# jlink.net
KiCad netlist of a schematic drawn in Altium Designer
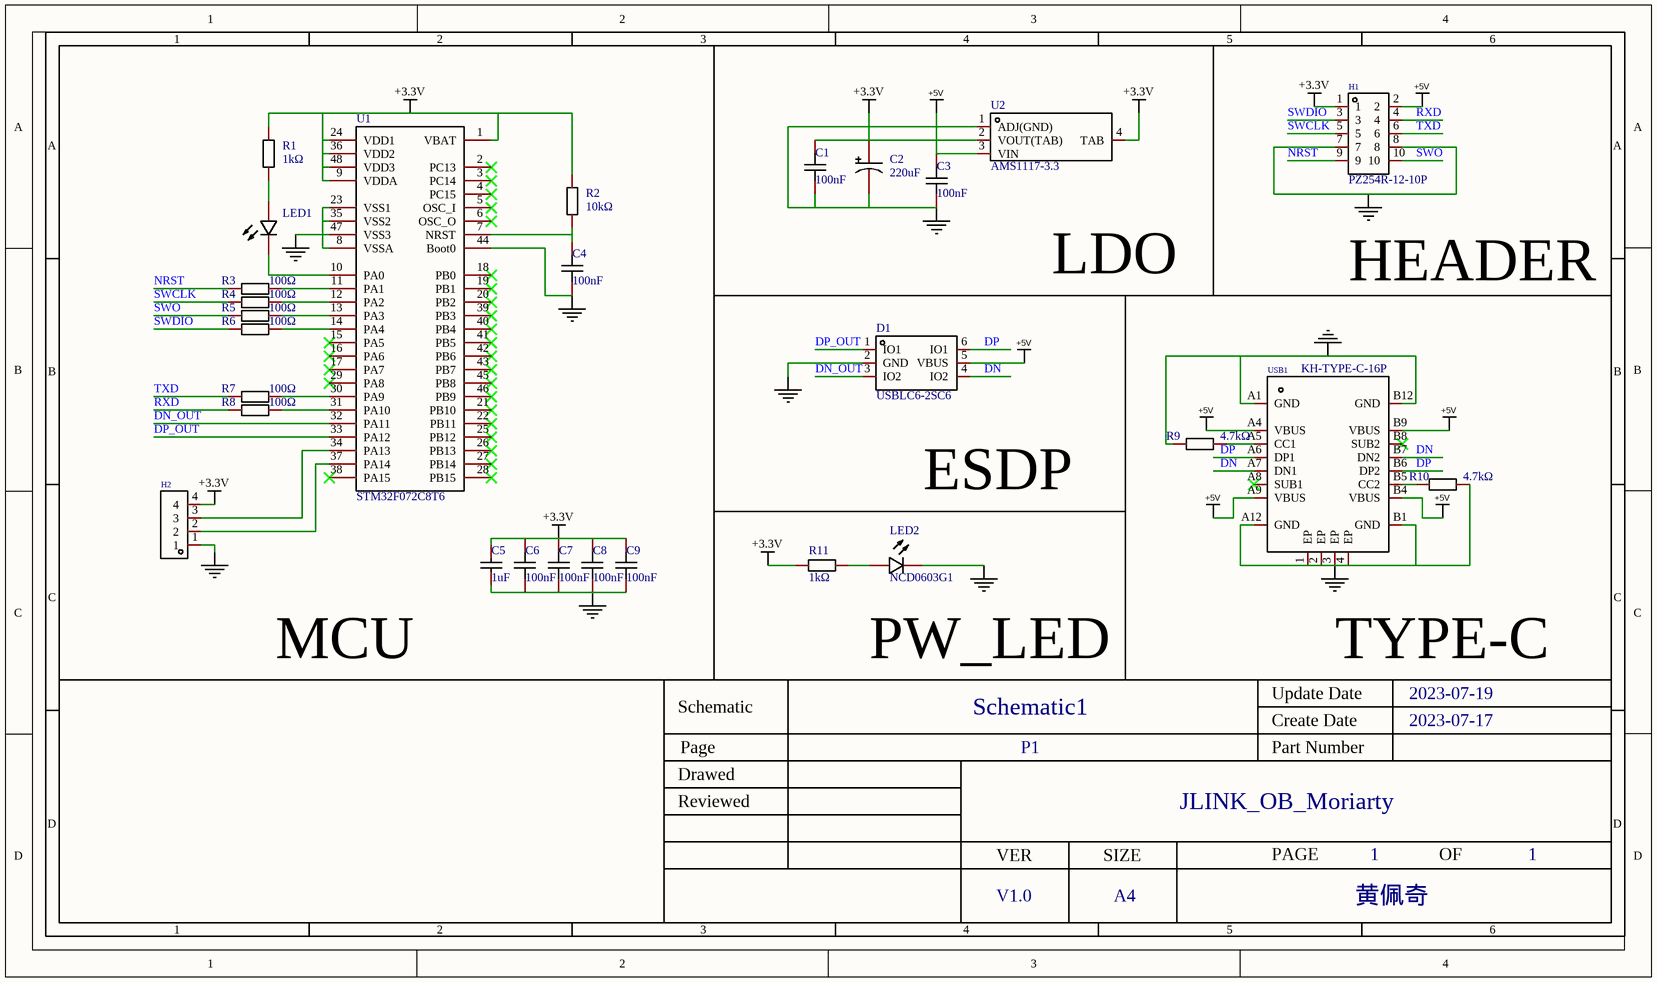
[diagram p0: jlink.schdoc]

(export (version "E")
  (design (tool "Eeschema 10.0.6"))
  (components
    (comp (ref "C1")
      (value "100nF")
      (description "容值:100nF;精度:±10%;额定电压:50V;材质(温度系数):X7R;")
      (fields
        (field (name "NAME") "100nF")
        (field (name "MANUFACTURER") "YAGEO(国巨)")
        (field (name "MANUFACTURER PART") "CC0603KRX7R9BB104")
      )
      (libsource (lib "altium-import") (part "root_1_CC0603KRX7R9BB104_"))
    )
    (comp (ref "C2")
      (value "220uF")
      (description "容值:220uF;精度:±20%;额定电压:50V;电容体直径:10mm;电容体长度:10mm;纹波电流:-;等效串联电阻:-;工作寿命:1000hrs@105℃;工作温度:-45℃~+105℃;")
      (fields
        (field (name "NAME") "220uF")
        (field (name "MANUFACTURER") "Nichicon(尼吉康)")
        (field (name "MANUFACTURER PART") "UWT1H221MNL1GS")
      )
      (libsource (lib "altium-import") (part "root_0_UWT1H221MNL1GS_"))
    )
    (comp (ref "C3")
      (value "100nF")
      (description "容值:100nF;精度:±10%;额定电压:50V;材质(温度系数):X7R;")
      (fields
        (field (name "NAME") "100nF")
        (field (name "MANUFACTURER") "YAGEO(国巨)")
        (field (name "MANUFACTURER PART") "CC0603KRX7R9BB104")
      )
      (libsource (lib "altium-import") (part "root_1_CC0603KRX7R9BB104_"))
    )
    (comp (ref "C4")
      (value "100nF")
      (description "容值:100nF;精度:±10%;额定电压:50V;材质(温度系数):X7R;")
      (fields
        (field (name "NAME") "100nF")
        (field (name "MANUFACTURER") "YAGEO(国巨)")
        (field (name "MANUFACTURER PART") "CC0603KRX7R9BB104")
      )
      (libsource (lib "altium-import") (part "root_1_CC0603KRX7R9BB104_"))
    )
    (comp (ref "C5")
      (value "1uF")
      (description "容值:1uF;精度:±10%;额定电压:25V;材质(温度系数):X7R;")
      (fields
        (field (name "NAME") "1uF")
        (field (name "MANUFACTURER") "FH(风华)")
        (field (name "MANUFACTURER PART") "0603B105K250NT")
      )
      (libsource (lib "altium-import") (part "root_1_0603B105K250NT_"))
    )
    (comp (ref "C6")
      (value "100nF")
      (description "容值:100nF;精度:±10%;额定电压:50V;材质(温度系数):X7R;")
      (fields
        (field (name "NAME") "100nF")
        (field (name "MANUFACTURER") "YAGEO(国巨)")
        (field (name "MANUFACTURER PART") "CC0603KRX7R9BB104")
      )
      (libsource (lib "altium-import") (part "root_1_CC0603KRX7R9BB104_"))
    )
    (comp (ref "C7")
      (value "100nF")
      (description "容值:100nF;精度:±10%;额定电压:50V;材质(温度系数):X7R;")
      (fields
        (field (name "NAME") "100nF")
        (field (name "MANUFACTURER") "YAGEO(国巨)")
        (field (name "MANUFACTURER PART") "CC0603KRX7R9BB104")
      )
      (libsource (lib "altium-import") (part "root_1_CC0603KRX7R9BB104_"))
    )
    (comp (ref "C8")
      (value "100nF")
      (description "容值:100nF;精度:±10%;额定电压:50V;材质(温度系数):X7R;")
      (fields
        (field (name "NAME") "100nF")
        (field (name "MANUFACTURER") "YAGEO(国巨)")
        (field (name "MANUFACTURER PART") "CC0603KRX7R9BB104")
      )
      (libsource (lib "altium-import") (part "root_1_CC0603KRX7R9BB104_"))
    )
    (comp (ref "C9")
      (value "100nF")
      (description "容值:100nF;精度:±10%;额定电压:50V;材质(温度系数):X7R;")
      (fields
        (field (name "NAME") "100nF")
        (field (name "MANUFACTURER") "YAGEO(国巨)")
        (field (name "MANUFACTURER PART") "CC0603KRX7R9BB104")
      )
      (libsource (lib "altium-import") (part "root_1_CC0603KRX7R9BB104_"))
    )
    (comp (ref "D1")
      (value "USBLC6-2SC6")
      (description "USBLC6-2SC6 Vrwm:5V 印记：UL26  ESD静电管静电放电(ESD)保护器件")
      (fields (field (name "NAME") "USBLC6-2SC6") (field (name "MANUFACTURER") "TECH PUBLIC(台舟)"))
      (libsource (lib "altium-import") (part "root_0_USBLC6-2SC6_C2827654_"))
    )
    (comp (ref "H1")
      (value "PZ254R-12-10P")
      (fields (field (name "NAME") "PZ254R-12-10P") (field (name "MANUFACTURER") "XFCN(兴飞)"))
      (libsource (lib "altium-import") (part "root_0_PZ254R-12-10P_"))
    )
    (comp (ref "H2")
      (value "PZ254V-11-04P")
      (fields (field (name "MANUFACTURER") "XFCN(兴飞)"))
      (libsource (lib "altium-import") (part "root_2_PZ254V-11-04P_"))
    )
    (comp (ref "LED1")
      (value "NCD0603W1")
      (description "发光颜色:白灯;")
      (fields (field (name "MANUFACTURER") "国星光电"))
      (libsource (lib "altium-import") (part "root_1_NCD0603W1_"))
    )
    (comp (ref "LED2")
      (value "NCD0603G1")
      (description "发光颜色:翠绿;")
      (fields (field (name "NAME") "NCD0603G1") (field (name "MANUFACTURER") "国星光电"))
      (libsource (lib "altium-import") (part "root_0_NCD0603G1_"))
    )
    (comp (ref "R1")
      (value "1kΩ")
      (description "电阻类型:厚膜电阻;阻值:1kΩ;精度:±1%;功率:100mW;")
      (fields
        (field (name "NAME") "1kΩ")
        (field (name "MANUFACTURER") "UNI-ROYAL(厚声)")
        (field (name "MANUFACTURER PART") "0603WAF1001T5E")
      )
      (libsource (lib "altium-import") (part "root_1_0603WAF1001T5E_"))
    )
    (comp (ref "R2")
      (value "10kΩ")
      (description "电阻类型:厚膜电阻;阻值:10kΩ;精度:±1%;功率:100mW;")
      (fields
        (field (name "NAME") "10kΩ")
        (field (name "MANUFACTURER") "UNI-ROYAL(厚声)")
        (field (name "MANUFACTURER PART") "0603WAF1002T5E")
      )
      (libsource (lib "altium-import") (part "root_1_0603WAF1002T5E_"))
    )
    (comp (ref "R3")
      (value "100Ω")
      (description "电阻类型:厚膜电阻;阻值:100Ω;精度:±1%;功率:100mW;")
      (fields
        (field (name "NAME") "100Ω")
        (field (name "MANUFACTURER") "UNI-ROYAL(厚声)")
        (field (name "MANUFACTURER PART") "0603WAF1000T5E")
      )
      (libsource (lib "altium-import") (part "root_2_0603WAF1000T5E_"))
    )
    (comp (ref "R4")
      (value "100Ω")
      (description "电阻类型:厚膜电阻;阻值:100Ω;精度:±1%;功率:100mW;")
      (fields
        (field (name "NAME") "100Ω")
        (field (name "MANUFACTURER") "UNI-ROYAL(厚声)")
        (field (name "MANUFACTURER PART") "0603WAF1000T5E")
      )
      (libsource (lib "altium-import") (part "root_2_0603WAF1000T5E_"))
    )
    (comp (ref "R5")
      (value "100Ω")
      (description "电阻类型:厚膜电阻;阻值:100Ω;精度:±1%;功率:100mW;")
      (fields
        (field (name "NAME") "100Ω")
        (field (name "MANUFACTURER") "UNI-ROYAL(厚声)")
        (field (name "MANUFACTURER PART") "0603WAF1000T5E")
      )
      (libsource (lib "altium-import") (part "root_2_0603WAF1000T5E_"))
    )
    (comp (ref "R6")
      (value "100Ω")
      (description "电阻类型:厚膜电阻;阻值:100Ω;精度:±1%;功率:100mW;")
      (fields
        (field (name "NAME") "100Ω")
        (field (name "MANUFACTURER") "UNI-ROYAL(厚声)")
        (field (name "MANUFACTURER PART") "0603WAF1000T5E")
      )
      (libsource (lib "altium-import") (part "root_2_0603WAF1000T5E_"))
    )
    (comp (ref "R7")
      (value "100Ω")
      (description "电阻类型:厚膜电阻;阻值:100Ω;精度:±1%;功率:100mW;")
      (fields
        (field (name "NAME") "100Ω")
        (field (name "MANUFACTURER") "UNI-ROYAL(厚声)")
        (field (name "MANUFACTURER PART") "0603WAF1000T5E")
      )
      (libsource (lib "altium-import") (part "root_2_0603WAF1000T5E_"))
    )
    (comp (ref "R8")
      (value "100Ω")
      (description "电阻类型:厚膜电阻;阻值:100Ω;精度:±1%;功率:100mW;")
      (fields
        (field (name "NAME") "100Ω")
        (field (name "MANUFACTURER") "UNI-ROYAL(厚声)")
        (field (name "MANUFACTURER PART") "0603WAF1000T5E")
      )
      (libsource (lib "altium-import") (part "root_2_0603WAF1000T5E_"))
    )
    (comp (ref "R9")
      (value "4.7kΩ")
      (description "电阻类型:厚膜电阻;阻值:4.7kΩ;精度:±1%;功率:100mW;")
      (fields
        (field (name "NAME") "4.7kΩ")
        (field (name "MANUFACTURER") "UNI-ROYAL(厚声)")
        (field (name "MANUFACTURER PART") "0603WAF4701T5E")
      )
      (libsource (lib "altium-import") (part "root_2_0603WAF4701T5E_"))
    )
    (comp (ref "R10")
      (value "4.7kΩ")
      (description "电阻类型:厚膜电阻;阻值:4.7kΩ;精度:±1%;功率:100mW;")
      (fields
        (field (name "NAME") "4.7kΩ")
        (field (name "MANUFACTURER") "UNI-ROYAL(厚声)")
        (field (name "MANUFACTURER PART") "0603WAF4701T5E")
      )
      (libsource (lib "altium-import") (part "root_2_0603WAF4701T5E_"))
    )
    (comp (ref "R11")
      (value "1kΩ")
      (description "电阻类型:厚膜电阻;阻值:1kΩ;精度:±1%;功率:100mW;")
      (fields
        (field (name "NAME") "1kΩ")
        (field (name "MANUFACTURER") "UNI-ROYAL(厚声)")
        (field (name "MANUFACTURER PART") "0603WAF1001T5E")
      )
      (libsource (lib "altium-import") (part "root_2_0603WAF1001T5E_"))
    )
    (comp (ref "U1")
      (value "STM32F072C8T6")
      (fields (field (name "NAME") "STM32F072C8T6") (field (name "MANUFACTURER") "ST(意法半导体)"))
      (libsource (lib "altium-import") (part "root_0_STM32F072C8T6_"))
    )
    (comp (ref "U2")
      (value "AMS1117-3.3")
      (description "输出类型:固定;输出极性:正;最大输入电压:18V;输出电压:3.3V;输出电流:1A;电源纹波抑制比(PSRR):60dB@(120Hz);")
      (fields (field (name "NAME") "AMS1117-3.3") (field (name "MANUFACTURER") "UMW(广东友台半导体)"))
      (libsource (lib "altium-import") (part "root_0_AMS1117-3.3_C347222_"))
    )
    (comp (ref "USB1")
      (value "KH-TYPE-C-16P")
      (description "Type-C母座 16PIN 立式四角贴板无压片")
      (fields (field (name "NAME") "KH-TYPE-C-16P") (field (name "MANUFACTURER") "kinghelm(金航标)"))
      (libsource (lib "altium-import") (part "root_0_KH-TYPE-C-16P_"))
    )
  )
  (nets
    (net (code "1") (name "+3.3V") (class "Default")
      (node (ref "C1") (pin "2") (pinfunction "2_2") (pintype "passive"))
      (node (ref "C2") (pin "1") (pinfunction "1_1") (pintype "passive"))
      (node (ref "C5") (pin "2") (pinfunction "2_2") (pintype "passive"))
      (node (ref "C6") (pin "2") (pinfunction "2_2") (pintype "passive"))
      (node (ref "C7") (pin "2") (pinfunction "2_2") (pintype "passive"))
      (node (ref "C8") (pin "2") (pinfunction "2_2") (pintype "passive"))
      (node (ref "C9") (pin "2") (pinfunction "2_2") (pintype "passive"))
      (node (ref "H1") (pin "1") (pinfunction "1_1") (pintype "passive"))
      (node (ref "H2") (pin "4") (pinfunction "4_4") (pintype "passive"))
      (node (ref "R1") (pin "2") (pinfunction "2_2") (pintype "passive"))
      (node (ref "R11") (pin "2") (pinfunction "2_2") (pintype "passive"))
      (node (ref "R2") (pin "2") (pinfunction "2_2") (pintype "passive"))
      (node (ref "U1") (pin "1") (pinfunction "VBAT_1") (pintype "passive"))
      (node (ref "U1") (pin "24") (pinfunction "VDD1_24") (pintype "passive"))
      (node (ref "U1") (pin "36") (pinfunction "VDD2_36") (pintype "passive"))
      (node (ref "U1") (pin "48") (pinfunction "VDD3_48") (pintype "passive"))
      (node (ref "U1") (pin "9") (pinfunction "VDDA_9") (pintype "passive"))
      (node (ref "U2") (pin "2") (pinfunction "VOUT(TAB)_2") (pintype "passive"))
      (node (ref "U2") (pin "4") (pinfunction "TAB_4") (pintype "passive"))
    )
    (net (code "2") (name "+5V") (class "Default")
      (node (ref "C3") (pin "2") (pinfunction "2_2") (pintype "passive"))
      (node (ref "D1") (pin "5") (pinfunction "VBUS_5") (pintype "passive"))
      (node (ref "H1") (pin "2") (pinfunction "2_2") (pintype "passive"))
      (node (ref "U2") (pin "3") (pinfunction "VIN_3") (pintype "passive"))
      (node (ref "USB1") (pin "A4") (pinfunction "VBUS_A4") (pintype "passive"))
      (node (ref "USB1") (pin "A9") (pinfunction "VBUS_A9") (pintype "passive"))
      (node (ref "USB1") (pin "B4") (pinfunction "VBUS_B4") (pintype "passive"))
      (node (ref "USB1") (pin "B9") (pinfunction "VBUS_B9") (pintype "passive"))
    )
    (net (code "3") (name "/DN") (class "Default")
      (node (ref "D1") (pin "4") (pinfunction "IO2_4") (pintype "passive"))
      (node (ref "USB1") (pin "A7") (pinfunction "DN1_A7") (pintype "passive"))
      (node (ref "USB1") (pin "B7") (pinfunction "DN2_B7") (pintype "passive"))
    )
    (net (code "4") (name "/DN_OUT") (class "Default")
      (node (ref "D1") (pin "3") (pinfunction "IO2_3") (pintype "passive"))
      (node (ref "U1") (pin "32") (pinfunction "PA11_32") (pintype "passive"))
    )
    (net (code "5") (name "/DP") (class "Default")
      (node (ref "D1") (pin "6") (pinfunction "IO1_6") (pintype "passive"))
      (node (ref "USB1") (pin "A6") (pinfunction "DP1_A6") (pintype "passive"))
      (node (ref "USB1") (pin "B6") (pinfunction "DP2_B6") (pintype "passive"))
    )
    (net (code "6") (name "/DP_OUT") (class "Default")
      (node (ref "D1") (pin "1") (pinfunction "IO1_1") (pintype "passive"))
      (node (ref "U1") (pin "33") (pinfunction "PA12_33") (pintype "passive"))
    )
    (net (code "7") (name "/NRST") (class "Default")
      (node (ref "H1") (pin "9") (pinfunction "9_9") (pintype "passive"))
      (node (ref "R3") (pin "2") (pinfunction "2_2") (pintype "passive"))
    )
    (net (code "8") (name "/RXD") (class "Default")
      (node (ref "H1") (pin "4") (pinfunction "4_4") (pintype "passive"))
      (node (ref "R8") (pin "2") (pinfunction "2_2") (pintype "passive"))
    )
    (net (code "9") (name "/SWCLK") (class "Default")
      (node (ref "H1") (pin "5") (pinfunction "5_5") (pintype "passive"))
      (node (ref "R4") (pin "2") (pinfunction "2_2") (pintype "passive"))
    )
    (net (code "10") (name "/SWDIO") (class "Default")
      (node (ref "H1") (pin "3") (pinfunction "3_3") (pintype "passive"))
      (node (ref "R6") (pin "2") (pinfunction "2_2") (pintype "passive"))
    )
    (net (code "11") (name "/SWO") (class "Default")
      (node (ref "H1") (pin "10") (pinfunction "10_10") (pintype "passive"))
      (node (ref "R5") (pin "2") (pinfunction "2_2") (pintype "passive"))
    )
    (net (code "12") (name "/TXD") (class "Default")
      (node (ref "H1") (pin "6") (pinfunction "6_6") (pintype "passive"))
      (node (ref "R7") (pin "2") (pinfunction "2_2") (pintype "passive"))
    )
    (net (code "13") (name "<NO NET>") (class "Default")
      (node (ref "C1") (pin "1") (pinfunction "1_1") (pintype "passive"))
      (node (ref "C2") (pin "2") (pinfunction "2_2") (pintype "passive"))
      (node (ref "C3") (pin "1") (pinfunction "1_1") (pintype "passive"))
      (node (ref "C4") (pin "1") (pinfunction "1_1") (pintype "passive"))
      (node (ref "C5") (pin "1") (pinfunction "1_1") (pintype "passive"))
      (node (ref "C6") (pin "1") (pinfunction "1_1") (pintype "passive"))
      (node (ref "C7") (pin "1") (pinfunction "1_1") (pintype "passive"))
      (node (ref "C8") (pin "1") (pinfunction "1_1") (pintype "passive"))
      (node (ref "C9") (pin "1") (pinfunction "1_1") (pintype "passive"))
      (node (ref "D1") (pin "2") (pinfunction "GND_2") (pintype "passive"))
      (node (ref "H1") (pin "7") (pinfunction "7_7") (pintype "passive"))
      (node (ref "H1") (pin "8") (pinfunction "8_8") (pintype "passive"))
      (node (ref "H2") (pin "1") (pinfunction "1_1") (pintype "passive"))
      (node (ref "LED2") (pin "1") (pinfunction "K_1") (pintype "passive"))
      (node (ref "R10") (pin "1") (pinfunction "1_1") (pintype "passive"))
      (node (ref "R9") (pin "2") (pinfunction "2_2") (pintype "passive"))
      (node (ref "U1") (pin "23") (pinfunction "VSS1_23") (pintype "passive"))
      (node (ref "U1") (pin "35") (pinfunction "VSS2_35") (pintype "passive"))
      (node (ref "U1") (pin "44") (pinfunction "Boot0_44") (pintype "passive"))
      (node (ref "U1") (pin "47") (pinfunction "VSS3_47") (pintype "passive"))
      (node (ref "U1") (pin "8") (pinfunction "VSSA_8") (pintype "passive"))
      (node (ref "U2") (pin "1") (pinfunction "ADJ(GND)_1") (pintype "passive"))
      (node (ref "USB1") (pin "1") (pinfunction "EP_1") (pintype "passive"))
      (node (ref "USB1") (pin "2") (pinfunction "EP_2") (pintype "passive"))
      (node (ref "USB1") (pin "3") (pinfunction "EP_3") (pintype "passive"))
      (node (ref "USB1") (pin "4") (pinfunction "EP_4") (pintype "passive"))
      (node (ref "USB1") (pin "A1") (pinfunction "GND_A1") (pintype "passive"))
      (node (ref "USB1") (pin "A12") (pinfunction "GND_A12") (pintype "passive"))
      (node (ref "USB1") (pin "B1") (pinfunction "GND_B1") (pintype "passive"))
      (node (ref "USB1") (pin "B12") (pinfunction "GND_B12") (pintype "passive"))
    )
    (net (code "14") (name "Net-(LED1-+)") (class "Default")
      (node (ref "LED1") (pin "2") (pinfunction "+_2") (pintype "passive"))
      (node (ref "R1") (pin "1") (pinfunction "1_1") (pintype "passive"))
    )
    (net (code "15") (name "Net-(LED1--)") (class "Default")
      (node (ref "LED1") (pin "1") (pinfunction "-_1") (pintype "passive"))
      (node (ref "U1") (pin "10") (pinfunction "PA0_10") (pintype "passive"))
    )
    (net (code "16") (name "Net-(LED2-A)") (class "Default")
      (node (ref "LED2") (pin "2") (pinfunction "A_2") (pintype "passive"))
      (node (ref "R11") (pin "1") (pinfunction "1_1") (pintype "passive"))
    )
    (net (code "17") (name "Net-(U1-NRST)") (class "Default")
      (node (ref "C4") (pin "2") (pinfunction "2_2") (pintype "passive"))
      (node (ref "R2") (pin "1") (pinfunction "1_1") (pintype "passive"))
      (node (ref "U1") (pin "7") (pinfunction "NRST_7") (pintype "passive"))
    )
    (net (code "18") (name "Net-(U1-PA1)") (class "Default")
      (node (ref "R3") (pin "1") (pinfunction "1_1") (pintype "passive"))
      (node (ref "U1") (pin "11") (pinfunction "PA1_11") (pintype "passive"))
    )
    (net (code "19") (name "Net-(U1-PA2)") (class "Default")
      (node (ref "R4") (pin "1") (pinfunction "1_1") (pintype "passive"))
      (node (ref "U1") (pin "12") (pinfunction "PA2_12") (pintype "passive"))
    )
    (net (code "20") (name "Net-(U1-PA3)") (class "Default")
      (node (ref "R5") (pin "1") (pinfunction "1_1") (pintype "passive"))
      (node (ref "U1") (pin "13") (pinfunction "PA3_13") (pintype "passive"))
    )
    (net (code "21") (name "Net-(U1-PA4)") (class "Default")
      (node (ref "R6") (pin "1") (pinfunction "1_1") (pintype "passive"))
      (node (ref "U1") (pin "14") (pinfunction "PA4_14") (pintype "passive"))
    )
    (net (code "22") (name "Net-(U1-PA9)") (class "Default")
      (node (ref "R7") (pin "1") (pinfunction "1_1") (pintype "passive"))
      (node (ref "U1") (pin "30") (pinfunction "PA9_30") (pintype "passive"))
    )
    (net (code "23") (name "Net-(U1-PA10)") (class "Default")
      (node (ref "R8") (pin "1") (pinfunction "1_1") (pintype "passive"))
      (node (ref "U1") (pin "31") (pinfunction "PA10_31") (pintype "passive"))
    )
    (net (code "24") (name "Net-(U1-PA13)") (class "Default")
      (node (ref "H2") (pin "3") (pinfunction "3_3") (pintype "passive"))
      (node (ref "U1") (pin "34") (pinfunction "PA13_34") (pintype "passive"))
    )
    (net (code "25") (name "Net-(U1-PA14)") (class "Default")
      (node (ref "H2") (pin "2") (pinfunction "2_2") (pintype "passive"))
      (node (ref "U1") (pin "37") (pinfunction "PA14_37") (pintype "passive"))
    )
    (net (code "26") (name "Net-(USB1-CC1)") (class "Default")
      (node (ref "R9") (pin "1") (pinfunction "1_1") (pintype "passive"))
      (node (ref "USB1") (pin "A5") (pinfunction "CC1_A5") (pintype "passive"))
    )
    (net (code "27") (name "Net-(USB1-CC2)") (class "Default")
      (node (ref "R10") (pin "2") (pinfunction "2_2") (pintype "passive"))
      (node (ref "USB1") (pin "B5") (pinfunction "CC2_B5") (pintype "passive"))
    )
    (net (code "28") (name "unconnected-(U1-OSC_I-Pad5)") (class "Default")
      (node (ref "U1") (pin "5") (pinfunction "OSC_I_5") (pintype "passive+no_connect"))
    )
    (net (code "29") (name "unconnected-(U1-OSC_O-Pad6)") (class "Default")
      (node (ref "U1") (pin "6") (pinfunction "OSC_O_6") (pintype "passive+no_connect"))
    )
    (net (code "30") (name "unconnected-(U1-PA5-Pad15)") (class "Default")
      (node (ref "U1") (pin "15") (pinfunction "PA5_15") (pintype "passive+no_connect"))
    )
    (net (code "31") (name "unconnected-(U1-PA6-Pad16)") (class "Default")
      (node (ref "U1") (pin "16") (pinfunction "PA6_16") (pintype "passive+no_connect"))
    )
    (net (code "32") (name "unconnected-(U1-PA7-Pad17)") (class "Default")
      (node (ref "U1") (pin "17") (pinfunction "PA7_17") (pintype "passive+no_connect"))
    )
    (net (code "33") (name "unconnected-(U1-PA8-Pad29)") (class "Default")
      (node (ref "U1") (pin "29") (pinfunction "PA8_29") (pintype "passive+no_connect"))
    )
    (net (code "34") (name "unconnected-(U1-PA15-Pad38)") (class "Default")
      (node (ref "U1") (pin "38") (pinfunction "PA15_38") (pintype "passive+no_connect"))
    )
    (net (code "35") (name "unconnected-(U1-PB0-Pad18)") (class "Default")
      (node (ref "U1") (pin "18") (pinfunction "PB0_18") (pintype "passive+no_connect"))
    )
    (net (code "36") (name "unconnected-(U1-PB1-Pad19)") (class "Default")
      (node (ref "U1") (pin "19") (pinfunction "PB1_19") (pintype "passive+no_connect"))
    )
    (net (code "37") (name "unconnected-(U1-PB2-Pad20)") (class "Default")
      (node (ref "U1") (pin "20") (pinfunction "PB2_20") (pintype "passive+no_connect"))
    )
    (net (code "38") (name "unconnected-(U1-PB3-Pad39)") (class "Default")
      (node (ref "U1") (pin "39") (pinfunction "PB3_39") (pintype "passive+no_connect"))
    )
    (net (code "39") (name "unconnected-(U1-PB4-Pad40)") (class "Default")
      (node (ref "U1") (pin "40") (pinfunction "PB4_40") (pintype "passive+no_connect"))
    )
    (net (code "40") (name "unconnected-(U1-PB5-Pad41)") (class "Default")
      (node (ref "U1") (pin "41") (pinfunction "PB5_41") (pintype "passive+no_connect"))
    )
    (net (code "41") (name "unconnected-(U1-PB6-Pad42)") (class "Default")
      (node (ref "U1") (pin "42") (pinfunction "PB6_42") (pintype "passive+no_connect"))
    )
    (net (code "42") (name "unconnected-(U1-PB7-Pad43)") (class "Default")
      (node (ref "U1") (pin "43") (pinfunction "PB7_43") (pintype "passive+no_connect"))
    )
    (net (code "43") (name "unconnected-(U1-PB8-Pad45)") (class "Default")
      (node (ref "U1") (pin "45") (pinfunction "PB8_45") (pintype "passive+no_connect"))
    )
    (net (code "44") (name "unconnected-(U1-PB9-Pad46)") (class "Default")
      (node (ref "U1") (pin "46") (pinfunction "PB9_46") (pintype "passive+no_connect"))
    )
    (net (code "45") (name "unconnected-(U1-PB10-Pad21)") (class "Default")
      (node (ref "U1") (pin "21") (pinfunction "PB10_21") (pintype "passive+no_connect"))
    )
    (net (code "46") (name "unconnected-(U1-PB11-Pad22)") (class "Default")
      (node (ref "U1") (pin "22") (pinfunction "PB11_22") (pintype "passive+no_connect"))
    )
    (net (code "47") (name "unconnected-(U1-PB12-Pad25)") (class "Default")
      (node (ref "U1") (pin "25") (pinfunction "PB12_25") (pintype "passive+no_connect"))
    )
    (net (code "48") (name "unconnected-(U1-PB13-Pad26)") (class "Default")
      (node (ref "U1") (pin "26") (pinfunction "PB13_26") (pintype "passive+no_connect"))
    )
    (net (code "49") (name "unconnected-(U1-PB14-Pad27)") (class "Default")
      (node (ref "U1") (pin "27") (pinfunction "PB14_27") (pintype "passive+no_connect"))
    )
    (net (code "50") (name "unconnected-(U1-PB15-Pad28)") (class "Default")
      (node (ref "U1") (pin "28") (pinfunction "PB15_28") (pintype "passive+no_connect"))
    )
    (net (code "51") (name "unconnected-(U1-PC13-Pad2)") (class "Default")
      (node (ref "U1") (pin "2") (pinfunction "PC13_2") (pintype "passive+no_connect"))
    )
    (net (code "52") (name "unconnected-(U1-PC14-Pad3)") (class "Default")
      (node (ref "U1") (pin "3") (pinfunction "PC14_3") (pintype "passive+no_connect"))
    )
    (net (code "53") (name "unconnected-(U1-PC15-Pad4)") (class "Default")
      (node (ref "U1") (pin "4") (pinfunction "PC15_4") (pintype "passive+no_connect"))
    )
    (net (code "54") (name "unconnected-(USB1-SUB1-PadA8)") (class "Default")
      (node (ref "USB1") (pin "A8") (pinfunction "SUB1_A8") (pintype "passive+no_connect"))
    )
    (net (code "55") (name "unconnected-(USB1-SUB2-PadB8)") (class "Default")
      (node (ref "USB1") (pin "B8") (pinfunction "SUB2_B8") (pintype "passive+no_connect"))
    )
  )
)
